# PR5008.net
KiCad netlist of a schematic drawn in EAGLE
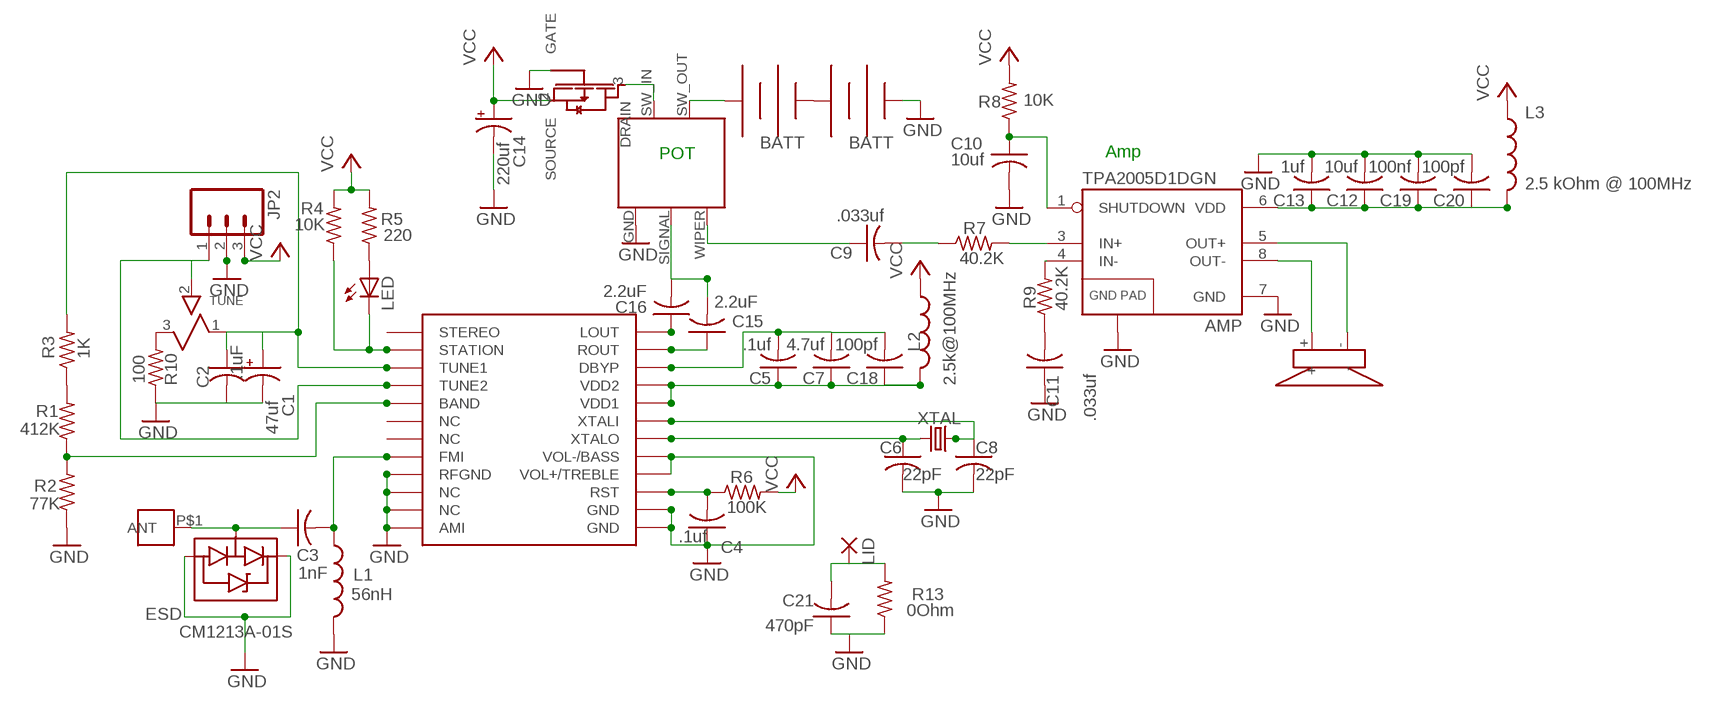
[diagram p0: schematic, sheet 1]

(export (version "E")
  (design (tool "Eeschema 10.0.6"))
  (components
    (comp (ref "AMP")
      (value "TPA2005D1DGN")
      (footprint "eagle-import:POWER-SOP8")
      (libsource (lib "eagle-import") (part "TPA2005D1DGN"))
    )
    (comp (ref "ANT")
      (value "M3_SCREW_POST")
      (footprint "eagle-import:M3_SCREW_POST")
      (libsource (lib "eagle-import") (part "M3_SCREW_POST"))
    )
    (comp (ref "C1")
      (value "47uf")
      (footprint "eagle-import:E2-5")
      (libsource (lib "eagle-import") (part "CPOL-USE2-5"))
    )
    (comp (ref "C2")
      (value ".1uF")
      (footprint "eagle-import:C0603")
      (libsource (lib "eagle-import") (part "C-USC0603"))
    )
    (comp (ref "C3")
      (value "1nF")
      (footprint "eagle-import:C0603")
      (libsource (lib "eagle-import") (part "C-USC0603"))
    )
    (comp (ref "C4")
      (value ".1uf")
      (footprint "eagle-import:C0603")
      (libsource (lib "eagle-import") (part "C-USC0603"))
    )
    (comp (ref "C5")
      (value ".1uf")
      (footprint "eagle-import:C0603")
      (libsource (lib "eagle-import") (part "C-USC0603"))
    )
    (comp (ref "C6")
      (value "22pF")
      (footprint "eagle-import:C0603")
      (libsource (lib "eagle-import") (part "C-USC0603"))
    )
    (comp (ref "C7")
      (value "4.7uf")
      (footprint "eagle-import:C0603")
      (libsource (lib "eagle-import") (part "C-USC0603"))
    )
    (comp (ref "C8")
      (value "22pF")
      (footprint "eagle-import:C0603")
      (libsource (lib "eagle-import") (part "C-USC0603"))
    )
    (comp (ref "C9")
      (value ".033uf")
      (footprint "eagle-import:C0603")
      (libsource (lib "eagle-import") (part "C-USC0603"))
    )
    (comp (ref "C10")
      (value "10uf")
      (footprint "eagle-import:C0603")
      (libsource (lib "eagle-import") (part "C-USC0603"))
    )
    (comp (ref "C11")
      (value ".033uf")
      (footprint "eagle-import:C0603")
      (libsource (lib "eagle-import") (part "C-USC0603"))
    )
    (comp (ref "C12")
      (value "10uf")
      (footprint "eagle-import:C0603")
      (libsource (lib "eagle-import") (part "C-USC0603"))
    )
    (comp (ref "C13")
      (value "1uf")
      (footprint "eagle-import:C0603")
      (libsource (lib "eagle-import") (part "C-USC0603"))
    )
    (comp (ref "C14")
      (value "220uf")
      (footprint "eagle-import:E2-5")
      (libsource (lib "eagle-import") (part "CPOL-USE2-5"))
    )
    (comp (ref "C15")
      (value "2.2uF")
      (footprint "eagle-import:C0603")
      (libsource (lib "eagle-import") (part "C-USC0603"))
    )
    (comp (ref "C16")
      (value "2.2uF")
      (footprint "eagle-import:C0603")
      (libsource (lib "eagle-import") (part "C-USC0603"))
    )
    (comp (ref "C18")
      (value "100pf")
      (footprint "eagle-import:C0603")
      (libsource (lib "eagle-import") (part "C-USC0603"))
    )
    (comp (ref "C19")
      (value "100nf")
      (footprint "eagle-import:C0603")
      (libsource (lib "eagle-import") (part "C-USC0603"))
    )
    (comp (ref "C20")
      (value "100pf")
      (footprint "eagle-import:C0603")
      (libsource (lib "eagle-import") (part "C-USC0603"))
    )
    (comp (ref "C21")
      (value "470pF")
      (footprint "eagle-import:C0603")
      (libsource (lib "eagle-import") (part "C-USC0603"))
    )
    (comp (ref "ESD")
      (value "CM1213A-01S")
      (footprint "eagle-import:SOT23-3")
      (libsource (lib "eagle-import") (part "CM1213A-01S"))
    )
    (comp (ref "FET")
      (value "SI2333DDS")
      (footprint "eagle-import:SI2333DDS")
      (libsource (lib "eagle-import") (part "SI2333DDS"))
    )
    (comp (ref "JP2")
      (value "M03LOCK")
      (footprint "eagle-import:1X03_LOCK")
      (libsource (lib "eagle-import") (part "M03LOCK"))
    )
    (comp (ref "L1")
      (value "56nH")
      (footprint "eagle-import:0603")
      (libsource (lib "eagle-import") (part "INDUCTOR0603"))
    )
    (comp (ref "L2")
      (value "2.5k@100MHz")
      (footprint "eagle-import:0603")
      (libsource (lib "eagle-import") (part "INDUCTOR0603"))
    )
    (comp (ref "L3")
      (value "2.5 kOhm @ 100MHz")
      (footprint "eagle-import:0603")
      (libsource (lib "eagle-import") (part "INDUCTOR0603"))
    )
    (comp (ref "LED")
      (value "LEDCHIPLED_0805")
      (footprint "eagle-import:CHIPLED_0805")
      (libsource (lib "eagle-import") (part "LEDCHIPLED_0805"))
    )
    (comp (ref "LID")
      (value "2,54/1,0")
      (footprint "eagle-import:2,54_1,0")
      (libsource (lib "eagle-import") (part "2,54/1,0"))
    )
    (comp (ref "R1")
      (value "412K")
      (footprint "eagle-import:R0603")
      (libsource (lib "eagle-import") (part "R-US_R0603"))
    )
    (comp (ref "R2")
      (value "77K")
      (footprint "eagle-import:R0603")
      (libsource (lib "eagle-import") (part "R-US_R0603"))
    )
    (comp (ref "R3")
      (value "1K")
      (footprint "eagle-import:R0603")
      (libsource (lib "eagle-import") (part "R-US_R0603"))
    )
    (comp (ref "R4")
      (value "10K")
      (footprint "eagle-import:R0603")
      (libsource (lib "eagle-import") (part "R-US_R0603"))
    )
    (comp (ref "R5")
      (value "220")
      (footprint "eagle-import:R0603")
      (libsource (lib "eagle-import") (part "R-US_R0603"))
    )
    (comp (ref "R6")
      (value "100K")
      (footprint "eagle-import:R0603")
      (libsource (lib "eagle-import") (part "R-US_R0603"))
    )
    (comp (ref "R7")
      (value "40.2K")
      (footprint "eagle-import:R0603")
      (libsource (lib "eagle-import") (part "R-US_R0603"))
    )
    (comp (ref "R8")
      (value "10K")
      (footprint "eagle-import:R0603")
      (libsource (lib "eagle-import") (part "R-US_R0603"))
    )
    (comp (ref "R9")
      (value "40.2K")
      (footprint "eagle-import:R0603")
      (libsource (lib "eagle-import") (part "R-US_R0603"))
    )
    (comp (ref "R10")
      (value "100")
      (footprint "eagle-import:R0603")
      (libsource (lib "eagle-import") (part "R-US_R0603"))
    )
    (comp (ref "R13")
      (value "0Ohm")
      (footprint "eagle-import:R0603")
      (libsource (lib "eagle-import") (part "R-US_R0603"))
    )
    (comp (ref "TUNE")
      (value "10k")
      (footprint "eagle-import:64XR_BOURNS_TRIMPOT")
      (libsource (lib "eagle-import") (part "64XR_BOURNS_TRIMPOT"))
    )
    (comp (ref "U$1")
      (value "BK-92_MPD_AA_BATT_CLIP")
      (footprint "eagle-import:BK-92_MPD_AA_BATT_CLIP")
      (libsource (lib "eagle-import") (part "BK-92_MPD_AA_BATT_CLIP"))
    )
    (comp (ref "U$2")
      (value "BK-92_MPD_AA_BATT_CLIP")
      (footprint "eagle-import:BK-92_MPD_AA_BATT_CLIP")
      (libsource (lib "eagle-import") (part "BK-92_MPD_AA_BATT_CLIP"))
    )
    (comp (ref "U$3")
      (value "CE32A_DAYTON_SPKR")
      (footprint "eagle-import:CE32A_DAYTON_SPKR")
      (libsource (lib "eagle-import") (part "CE32A_DAYTON_SPKR"))
    )
    (comp (ref "U$4")
      (value "SI4831_FM_IC")
      (footprint "eagle-import:SI4831_FM_IC")
      (libsource (lib "eagle-import") (part "SI4831_FM_IC"))
    )
    (comp (ref "U$5")
      (value "RV170SF_TAIWANA_POT_SW")
      (footprint "eagle-import:RV170SF_TAIWANA_POT_SW")
      (libsource (lib "eagle-import") (part "RV170SF_TAIWANA_POT_SW"))
    )
    (comp (ref "XTAL")
      (value "CRYSTAL32-SMD")
      (footprint "eagle-import:CRYSTAL-32KHZ-SMD")
      (libsource (lib "eagle-import") (part "CRYSTAL32-SMD"))
    )
  )
  (nets
    (net (code "1") (name "GND") (class "Default")
      (node (ref "AMP") (pin "7") (pinfunction "GND_7") (pintype "power_in"))
      (node (ref "AMP") (pin "9") (pinfunction "GND_9") (pintype "power_in"))
      (node (ref "C1") (pin "-") (pinfunction "-_-") (pintype "passive"))
      (node (ref "C10") (pin "2") (pinfunction "2_2") (pintype "passive"))
      (node (ref "C11") (pin "1") (pinfunction "1_1") (pintype "passive"))
      (node (ref "C12") (pin "2") (pinfunction "2_2") (pintype "passive"))
      (node (ref "C13") (pin "2") (pinfunction "2_2") (pintype "passive"))
      (node (ref "C14") (pin "-") (pinfunction "-_-") (pintype "passive"))
      (node (ref "C19") (pin "2") (pinfunction "2_2") (pintype "passive"))
      (node (ref "C2") (pin "2") (pinfunction "2_2") (pintype "passive"))
      (node (ref "C20") (pin "2") (pinfunction "2_2") (pintype "passive"))
      (node (ref "C21") (pin "1") (pinfunction "1_1") (pintype "passive"))
      (node (ref "C4") (pin "1") (pinfunction "1_1") (pintype "passive"))
      (node (ref "C6") (pin "2") (pinfunction "2_2") (pintype "passive"))
      (node (ref "C8") (pin "2") (pinfunction "2_2") (pintype "passive"))
      (node (ref "ESD") (pin "2") (pinfunction "VP_2") (pintype "passive"))
      (node (ref "ESD") (pin "3") (pinfunction "VN_3") (pintype "passive"))
      (node (ref "FET") (pin "1") (pinfunction "GATE_1") (pintype "bidirectional"))
      (node (ref "JP2") (pin "2") (pinfunction "2_2") (pintype "passive"))
      (node (ref "L1") (pin "2") (pinfunction "2_2") (pintype "passive"))
      (node (ref "R10") (pin "1") (pinfunction "1_1") (pintype "passive"))
      (node (ref "R13") (pin "1") (pinfunction "1_1") (pintype "passive"))
      (node (ref "R2") (pin "1") (pinfunction "1_1") (pintype "passive"))
      (node (ref "U$2") (pin "NEG") (pinfunction "NEG_NEG") (pintype "bidirectional"))
      (node (ref "U$2") (pin "NEG@2") (pinfunction "NEG_NEG@2") (pintype "bidirectional"))
      (node (ref "U$4") (pin "AMI") (pinfunction "AMI_AMI") (pintype "bidirectional"))
      (node (ref "U$4") (pin "GND") (pinfunction "GND_GND") (pintype "bidirectional"))
      (node (ref "U$4") (pin "GND@2") (pinfunction "GND_GND@2") (pintype "bidirectional"))
      (node (ref "U$4") (pin "NC@3") (pinfunction "NC_NC@3") (pintype "bidirectional"))
      (node (ref "U$4") (pin "NC@4") (pinfunction "NC_NC@4") (pintype "bidirectional"))
      (node (ref "U$4") (pin "RFGND") (pinfunction "RFGND_RFGND") (pintype "bidirectional"))
      (node (ref "U$4") (pin "VOL+/TREBLE") (pinfunction "VOL+/TREBLE_VOL+/TREBLE") (pintype "bidirectional"))
      (node (ref "U$4") (pin "VOL-/BASS") (pinfunction "VOL-/BASS_VOL-/BASS") (pintype "bidirectional"))
      (node (ref "U$5") (pin "GND") (pinfunction "GND_GND") (pintype "bidirectional"))
    )
    (net (code "2") (name "Net-(AMP-IN+)") (class "Default")
      (node (ref "AMP") (pin "3") (pinfunction "IN+_3") (pintype "bidirectional"))
      (node (ref "R7") (pin "2") (pinfunction "2_2") (pintype "passive"))
    )
    (net (code "3") (name "Net-(AMP-IN-)") (class "Default")
      (node (ref "AMP") (pin "4") (pinfunction "IN-_4") (pintype "bidirectional"))
      (node (ref "R9") (pin "2") (pinfunction "2_2") (pintype "passive"))
    )
    (net (code "4") (name "Net-(AMP-OUT+)") (class "Default")
      (node (ref "AMP") (pin "5") (pinfunction "OUT+_5") (pintype "bidirectional"))
      (node (ref "U$3") (pin "-") (pinfunction "-_-") (pintype "bidirectional"))
    )
    (net (code "5") (name "Net-(AMP-OUT-)") (class "Default")
      (node (ref "AMP") (pin "8") (pinfunction "OUT-_8") (pintype "bidirectional"))
      (node (ref "U$3") (pin "+") (pinfunction "+_+") (pintype "bidirectional"))
    )
    (net (code "6") (name "Net-(AMP-SHUTDOWN)") (class "Default")
      (node (ref "AMP") (pin "1") (pinfunction "SHUTDOWN_1") (pintype "input"))
      (node (ref "C10") (pin "1") (pinfunction "1_1") (pintype "passive"))
      (node (ref "R8") (pin "1") (pinfunction "1_1") (pintype "passive"))
    )
    (net (code "7") (name "Net-(AMP-VDD)") (class "Default")
      (node (ref "AMP") (pin "6") (pinfunction "VDD_6") (pintype "power_in"))
      (node (ref "C12") (pin "1") (pinfunction "1_1") (pintype "passive"))
      (node (ref "C13") (pin "1") (pinfunction "1_1") (pintype "passive"))
      (node (ref "C19") (pin "1") (pinfunction "1_1") (pintype "passive"))
      (node (ref "C20") (pin "1") (pinfunction "1_1") (pintype "passive"))
      (node (ref "L3") (pin "2") (pinfunction "2_2") (pintype "passive"))
    )
    (net (code "8") (name "Net-(ANT-ANT)") (class "Default")
      (node (ref "ANT") (pin "P$1") (pinfunction "ANT_P$1") (pintype "bidirectional"))
      (node (ref "C3") (pin "1") (pinfunction "1_1") (pintype "passive"))
      (node (ref "ESD") (pin "1") (pinfunction "CH_1") (pintype "passive"))
    )
    (net (code "9") (name "Net-(C1-Pad+)") (class "Default")
      (node (ref "C1") (pin "+") (pinfunction "+_+") (pintype "passive"))
      (node (ref "C2") (pin "1") (pinfunction "1_1") (pintype "passive"))
      (node (ref "R3") (pin "2") (pinfunction "2_2") (pintype "passive"))
      (node (ref "TUNE") (pin "1") (pinfunction "1_1") (pintype "bidirectional"))
      (node (ref "U$4") (pin "TUNE1") (pinfunction "TUNE1_TUNE1") (pintype "bidirectional"))
    )
    (net (code "10") (name "Net-(C3-Pad2)") (class "Default")
      (node (ref "C3") (pin "2") (pinfunction "2_2") (pintype "passive"))
      (node (ref "L1") (pin "1") (pinfunction "1_1") (pintype "passive"))
      (node (ref "U$4") (pin "FMI") (pinfunction "FMI_FMI") (pintype "bidirectional"))
    )
    (net (code "11") (name "Net-(C4-Pad2)") (class "Default")
      (node (ref "C4") (pin "2") (pinfunction "2_2") (pintype "passive"))
      (node (ref "R6") (pin "1") (pinfunction "1_1") (pintype "passive"))
      (node (ref "U$4") (pin "RST") (pinfunction "RST_RST") (pintype "bidirectional"))
    )
    (net (code "12") (name "Net-(C9-Pad1)") (class "Default")
      (node (ref "C9") (pin "1") (pinfunction "1_1") (pintype "passive"))
      (node (ref "U$5") (pin "WIPER") (pinfunction "WIPER_WIPER") (pintype "bidirectional"))
    )
    (net (code "13") (name "Net-(C9-Pad2)") (class "Default")
      (node (ref "C9") (pin "2") (pinfunction "2_2") (pintype "passive"))
      (node (ref "R7") (pin "1") (pinfunction "1_1") (pintype "passive"))
    )
    (net (code "14") (name "Net-(C11-Pad2)") (class "Default")
      (node (ref "C11") (pin "2") (pinfunction "2_2") (pintype "passive"))
      (node (ref "R9") (pin "1") (pinfunction "1_1") (pintype "passive"))
    )
    (net (code "15") (name "Net-(C15-Pad1)") (class "Default")
      (node (ref "C15") (pin "1") (pinfunction "1_1") (pintype "passive"))
      (node (ref "U$4") (pin "ROUT") (pinfunction "ROUT_ROUT") (pintype "bidirectional"))
    )
    (net (code "16") (name "Net-(C15-Pad2)") (class "Default")
      (node (ref "C15") (pin "2") (pinfunction "2_2") (pintype "passive"))
      (node (ref "C16") (pin "2") (pinfunction "2_2") (pintype "passive"))
      (node (ref "U$5") (pin "SIGNAL") (pinfunction "SIGNAL_SIGNAL") (pintype "bidirectional"))
    )
    (net (code "17") (name "Net-(C16-Pad1)") (class "Default")
      (node (ref "C16") (pin "1") (pinfunction "1_1") (pintype "passive"))
      (node (ref "U$4") (pin "LOUT") (pinfunction "LOUT_LOUT") (pintype "bidirectional"))
    )
    (net (code "18") (name "Net-(C18-Pad1)") (class "Default")
      (node (ref "C18") (pin "1") (pinfunction "1_1") (pintype "passive"))
      (node (ref "C5") (pin "1") (pinfunction "1_1") (pintype "passive"))
      (node (ref "C7") (pin "1") (pinfunction "1_1") (pintype "passive"))
      (node (ref "L2") (pin "2") (pinfunction "2_2") (pintype "passive"))
      (node (ref "U$4") (pin "VDD1") (pinfunction "VDD1_VDD1") (pintype "bidirectional"))
      (node (ref "U$4") (pin "VDD2") (pinfunction "VDD2_VDD2") (pintype "bidirectional"))
    )
    (net (code "19") (name "Net-(C18-Pad2)") (class "Default")
      (node (ref "C18") (pin "2") (pinfunction "2_2") (pintype "passive"))
      (node (ref "C5") (pin "2") (pinfunction "2_2") (pintype "passive"))
      (node (ref "C7") (pin "2") (pinfunction "2_2") (pintype "passive"))
      (node (ref "U$4") (pin "DBYP") (pinfunction "DBYP_DBYP") (pintype "bidirectional"))
    )
    (net (code "20") (name "Net-(FET-DRAIN)") (class "Default")
      (node (ref "FET") (pin "3") (pinfunction "DRAIN_3") (pintype "bidirectional"))
      (node (ref "U$5") (pin "SW_IN") (pinfunction "SW_IN_SW_IN") (pintype "bidirectional"))
    )
    (net (code "21") (name "Net-(JP2-Pad1)") (class "Default")
      (node (ref "JP2") (pin "1") (pinfunction "1_1") (pintype "passive"))
      (node (ref "TUNE") (pin "2") (pinfunction "2_2") (pintype "bidirectional"))
      (node (ref "U$4") (pin "TUNE2") (pinfunction "TUNE2_TUNE2") (pintype "bidirectional"))
    )
    (net (code "22") (name "Net-(LED-PadA)") (class "Default")
      (node (ref "LED") (pin "A") (pinfunction "A_A") (pintype "passive"))
      (node (ref "R5") (pin "1") (pinfunction "1_1") (pintype "passive"))
    )
    (net (code "23") (name "Net-(LED-PadC)") (class "Default")
      (node (ref "LED") (pin "C") (pinfunction "C_C") (pintype "passive"))
      (node (ref "R4") (pin "1") (pinfunction "1_1") (pintype "passive"))
      (node (ref "U$4") (pin "STATION") (pinfunction "STATION_STATION") (pintype "bidirectional"))
    )
    (net (code "24") (name "Net-(LID-P)") (class "Default")
      (node (ref "C21") (pin "2") (pinfunction "2_2") (pintype "passive"))
      (node (ref "LID") (pin "1") (pinfunction "P_1") (pintype "passive"))
      (node (ref "R13") (pin "2") (pinfunction "2_2") (pintype "passive"))
    )
    (net (code "25") (name "Net-(R1-Pad1)") (class "Default")
      (node (ref "R1") (pin "1") (pinfunction "1_1") (pintype "passive"))
      (node (ref "R2") (pin "2") (pinfunction "2_2") (pintype "passive"))
      (node (ref "U$4") (pin "BAND") (pinfunction "BAND_BAND") (pintype "bidirectional"))
    )
    (net (code "26") (name "Net-(R1-Pad2)") (class "Default")
      (node (ref "R1") (pin "2") (pinfunction "2_2") (pintype "passive"))
      (node (ref "R3") (pin "1") (pinfunction "1_1") (pintype "passive"))
    )
    (net (code "27") (name "Net-(R10-Pad2)") (class "Default")
      (node (ref "R10") (pin "2") (pinfunction "2_2") (pintype "passive"))
      (node (ref "TUNE") (pin "3") (pinfunction "3_3") (pintype "bidirectional"))
    )
    (net (code "28") (name "Net-(U$1-NEG-PadNEG@2)") (class "Default")
      (node (ref "U$1") (pin "NEG") (pinfunction "NEG_NEG") (pintype "bidirectional"))
      (node (ref "U$1") (pin "NEG@2") (pinfunction "NEG_NEG@2") (pintype "bidirectional"))
      (node (ref "U$2") (pin "POS") (pinfunction "POS_POS") (pintype "bidirectional"))
      (node (ref "U$2") (pin "POS@2") (pinfunction "POS_POS@2") (pintype "bidirectional"))
    )
    (net (code "29") (name "Net-(U$1-POS-PadPOS@2)") (class "Default")
      (node (ref "U$1") (pin "POS") (pinfunction "POS_POS") (pintype "bidirectional"))
      (node (ref "U$1") (pin "POS@2") (pinfunction "POS_POS@2") (pintype "bidirectional"))
      (node (ref "U$5") (pin "SW_OUT") (pinfunction "SW_OUT_SW_OUT") (pintype "bidirectional"))
    )
    (net (code "30") (name "Net-(XTAL-1)") (class "Default")
      (node (ref "C8") (pin "1") (pinfunction "1_1") (pintype "passive"))
      (node (ref "U$4") (pin "XTALI") (pinfunction "XTALI_XTALI") (pintype "bidirectional"))
      (node (ref "XTAL") (pin "X1") (pinfunction "1_X1") (pintype "passive"))
    )
    (net (code "31") (name "Net-(XTAL-2)") (class "Default")
      (node (ref "C6") (pin "1") (pinfunction "1_1") (pintype "passive"))
      (node (ref "U$4") (pin "XTALO") (pinfunction "XTALO_XTALO") (pintype "bidirectional"))
      (node (ref "XTAL") (pin "X2") (pinfunction "2_X2") (pintype "passive"))
    )
    (net (code "32") (name "VCC") (class "Default")
      (node (ref "C14") (pin "+") (pinfunction "+_+") (pintype "passive"))
      (node (ref "FET") (pin "2") (pinfunction "SOURCE_2") (pintype "bidirectional"))
      (node (ref "JP2") (pin "3") (pinfunction "3_3") (pintype "passive"))
      (node (ref "L2") (pin "1") (pinfunction "1_1") (pintype "passive"))
      (node (ref "L3") (pin "1") (pinfunction "1_1") (pintype "passive"))
      (node (ref "R4") (pin "2") (pinfunction "2_2") (pintype "passive"))
      (node (ref "R5") (pin "2") (pinfunction "2_2") (pintype "passive"))
      (node (ref "R6") (pin "2") (pinfunction "2_2") (pintype "passive"))
      (node (ref "R8") (pin "2") (pinfunction "2_2") (pintype "passive"))
    )
    (net (code "33") (name "unconnected-(U$4-NC-PadNC@2)") (class "Default")
      (node (ref "U$4") (pin "NC@2") (pinfunction "NC_NC@2") (pintype "bidirectional"))
    )
    (net (code "34") (name "unconnected-(U$4-PadNC)") (class "Default")
      (node (ref "U$4") (pin "NC") (pinfunction "NC_NC") (pintype "bidirectional"))
    )
    (net (code "35") (name "unconnected-(U$4-PadSTEREO)") (class "Default")
      (node (ref "U$4") (pin "STEREO") (pinfunction "STEREO_STEREO") (pintype "bidirectional"))
    )
  )
)
